# GD32.net
KiCad netlist of a schematic drawn in Altium Designer
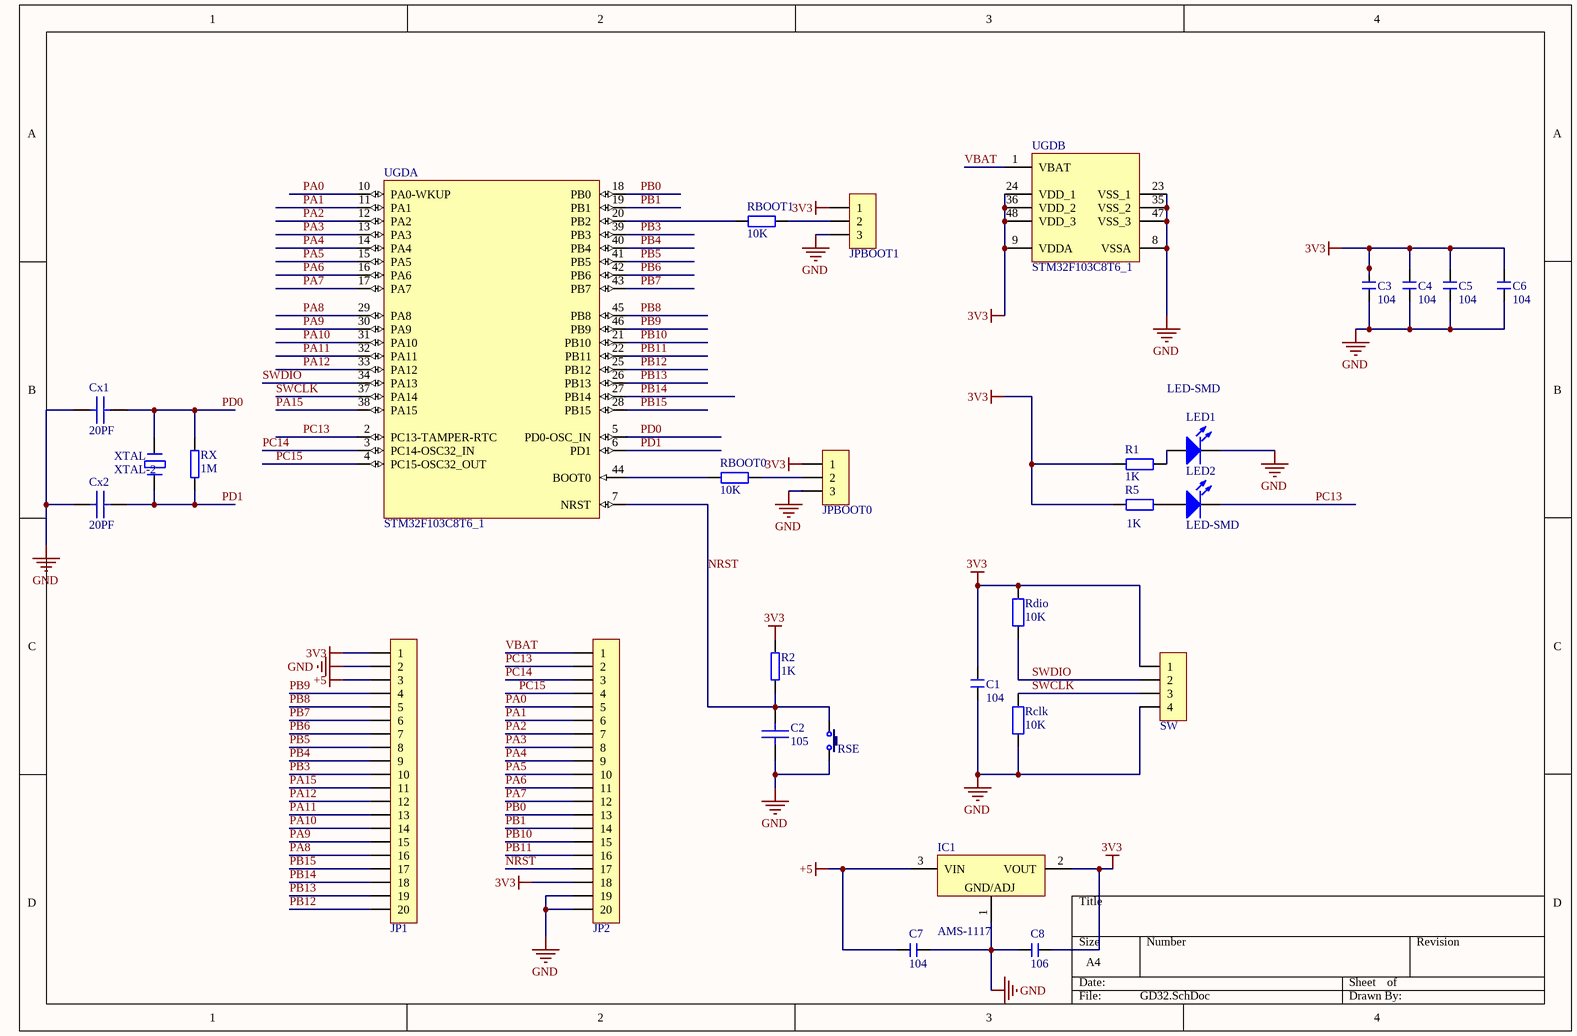
[diagram p0: GD32.SchDoc]

(export (version "E")
  (design (tool "Eeschema 10.0.6"))
  (components
    (comp (ref "C1")
      (value "104")
      (footprint "C 0805")
      (description "无极性贴片电容")
      (fields (field (name "版权归属") "源创客"))
      (libsource (lib "电阻-电容-电感") (part "C"))
    )
    (comp (ref "C2")
      (value "105")
      (footprint "LC-0805_C")
      (description "贴片电容（无极性）")
      (libsource (lib "FLY") (part "CAP-NPL-SMD"))
    )
    (comp (ref "C3")
      (value "104")
      (footprint "C 0805")
      (description "无极性贴片电容")
      (fields (field (name "版权归属") "源创客"))
      (libsource (lib "电阻-电容-电感") (part "C"))
    )
    (comp (ref "C4")
      (value "104")
      (footprint "C 0805")
      (description "无极性贴片电容")
      (fields (field (name "版权归属") "源创客"))
      (libsource (lib "电阻-电容-电感") (part "C"))
    )
    (comp (ref "C5")
      (value "104")
      (footprint "C 0805")
      (description "无极性贴片电容")
      (fields (field (name "版权归属") "源创客"))
      (libsource (lib "电阻-电容-电感") (part "C"))
    )
    (comp (ref "C6")
      (value "104")
      (footprint "C 0805")
      (description "无极性贴片电容")
      (fields (field (name "版权归属") "源创客"))
      (libsource (lib "电阻-电容-电感") (part "C"))
    )
    (comp (ref "C7")
      (value "104")
      (footprint "C 0805")
      (description "无极性贴片电容")
      (fields (field (name "版权归属") "源创客"))
      (libsource (lib "电阻-电容-电感") (part "C"))
    )
    (comp (ref "C8")
      (value "106")
      (footprint "C 0805")
      (description "无极性贴片电容")
      (fields (field (name "版权归属") "源创客"))
      (libsource (lib "电阻-电容-电感") (part "C"))
    )
    (comp (ref "Cx1")
      (value "20PF")
      (footprint "LC-0805_C")
      (description "贴片电容（无极性）")
      (libsource (lib "FLY") (part "CAP-NPL-SMD"))
    )
    (comp (ref "Cx2")
      (value "20PF")
      (footprint "LC-0805_C")
      (description "贴片电容（无极性）")
      (libsource (lib "FLY") (part "CAP-NPL-SMD"))
    )
    (comp (ref "IC1")
      (value "AMS-1117")
      (footprint "LC-SOT-223")
      (description "线性稳压器")
      (libsource (lib "FLY") (part "AMS-1117"))
    )
    (comp (ref "JP1")
      (value "HDR-1X20")
      (footprint "HDR-1X20")
      (description "20P接插件")
      (fields (field (name "版权归属") "源创客"))
      (libsource (lib "接插件") (part "Header 20"))
    )
    (comp (ref "JP2")
      (value "HDR-1X20")
      (footprint "HDR-1X20")
      (description "20P接插件")
      (fields (field (name "版权归属") "源创客"))
      (libsource (lib "接插件") (part "Header 20"))
    )
    (comp (ref "JPBOOT0")
      (value "HDR-1X3")
      (footprint "HDR-1X3")
      (description "3P接插件")
      (fields (field (name "版权归属") "源创客"))
      (libsource (lib "接插件") (part "Header 3"))
    )
    (comp (ref "JPBOOT1")
      (value "HDR-1X3")
      (footprint "HDR-1X3")
      (description "3P接插件")
      (fields (field (name "版权归属") "源创客"))
      (libsource (lib "接插件") (part "Header 3"))
    )
    (comp (ref "LED1")
      (value "LED-SMD")
      (footprint "LC-0805_LED_S1")
      (description "贴片LED")
      (fields
        (field (name "MANUFACTURER") "Generic Components")
        (field (name "PUBLISHER") "Altium Hobart Technology Centre")
      )
      (libsource (lib "FLY") (part "LED-SMD"))
    )
    (comp (ref "LED2")
      (value "LED-SMD")
      (footprint "LC-0805_LED_S1")
      (description "贴片LED")
      (fields
        (field (name "MANUFACTURER") "Generic Components")
        (field (name "PUBLISHER") "Altium Hobart Technology Centre")
      )
      (libsource (lib "FLY") (part "LED-SMD"))
    )
    (comp (ref "R1")
      (value "1K")
      (footprint "R 0805")
      (description "贴片电阻")
      (fields (field (name "版权归属") "源创客"))
      (libsource (lib "电阻-电容-电感") (part "R"))
    )
    (comp (ref "R2")
      (value "1K")
      (footprint "LC-0805_R")
      (description "电阻")
      (libsource (lib "FLY") (part "RES"))
    )
    (comp (ref "R5")
      (value "1K")
      (footprint "R 0805")
      (description "贴片电阻")
      (fields (field (name "版权归属") "源创客"))
      (libsource (lib "电阻-电容-电感") (part "R"))
    )
    (comp (ref "RBOOT0")
      (value "10K")
      (footprint "R 0805")
      (description "贴片电阻")
      (fields (field (name "版权归属") "源创客"))
      (libsource (lib "电阻-电容-电感") (part "R"))
    )
    (comp (ref "RBOOT1")
      (value "10K")
      (footprint "R 0805")
      (description "贴片电阻")
      (fields (field (name "版权归属") "源创客"))
      (libsource (lib "电阻-电容-电感") (part "R"))
    )
    (comp (ref "Rclk")
      (value "10K")
      (footprint "R 0805")
      (description "贴片电阻")
      (fields (field (name "版权归属") "源创客"))
      (libsource (lib "电阻-电容-电感") (part "R"))
    )
    (comp (ref "Rdio")
      (value "10K")
      (footprint "R 0805")
      (description "贴片电阻")
      (fields (field (name "版权归属") "源创客"))
      (libsource (lib "电阻-电容-电感") (part "R"))
    )
    (comp (ref "RSE")
      (value "3x6x5")
      (footprint "TSW SMD-3*6*2.5")
      (description "3x6轻触开关")
      (fields (field (name "版权归属") "源创客"))
      (libsource (lib "按键-开关") (part "TSW 3x6"))
    )
    (comp (ref "RX")
      (value "1M")
      (footprint "LC-0805_R")
      (description "电阻")
      (libsource (lib "FLY") (part "RES"))
    )
    (comp (ref "SW")
      (value "HDR-1X4")
      (footprint "HDR-1X4")
      (description "4P接插件")
      (fields (field (name "版权归属") "源创客"))
      (libsource (lib "接插件") (part "Header 4"))
    )
    (comp (ref "UGD")
      (value "STM32F103C8T6_1")
      (footprint "LQFP48 7X7_M")
      (description "Flaah:64/RAM:20/IO:36")
      (fields (field (name "版权归属") "源创客"))
      (libsource (lib "STM32系列单片机") (part "STM32F103C8T6_1"))
    )
    (comp (ref "XTAL")
      (value "XTAL-2")
      (footprint "LC-HC-49S")
      (description "晶体振荡器")
      (libsource (lib "FLY") (part "XTAL-2"))
    )
  )
  (nets
    (net (code "1") (name "+5") (class "Default")
      (node (ref "C7") (pin "1") (pinfunction "1_1") (pintype "passive"))
      (node (ref "IC1") (pin "3") (pinfunction "VIN_3") (pintype "passive"))
      (node (ref "JP1") (pin "3") (pinfunction "3_3") (pintype "passive"))
    )
    (net (code "2") (name "/NRST") (class "Default")
      (node (ref "C2") (pin "2") (pinfunction "2_2") (pintype "passive"))
      (node (ref "JP2") (pin "17") (pinfunction "17_17") (pintype "passive"))
      (node (ref "R2") (pin "1") (pinfunction "1_1") (pintype "passive"))
      (node (ref "RSE") (pin "1") (pinfunction "1_1") (pintype "passive"))
      (node (ref "UGD") (pin "7") (pinfunction "NRST_7") (pintype "bidirectional"))
    )
    (net (code "3") (name "/PA0") (class "Default")
      (node (ref "JP2") (pin "5") (pinfunction "5_5") (pintype "passive"))
      (node (ref "UGD") (pin "10") (pinfunction "PA0-WKUP_10") (pintype "bidirectional"))
    )
    (net (code "4") (name "/PA1") (class "Default")
      (node (ref "JP2") (pin "6") (pinfunction "6_6") (pintype "passive"))
      (node (ref "UGD") (pin "11") (pinfunction "PA1_11") (pintype "bidirectional"))
    )
    (net (code "5") (name "/PA2") (class "Default")
      (node (ref "JP2") (pin "7") (pinfunction "7_7") (pintype "passive"))
      (node (ref "UGD") (pin "12") (pinfunction "PA2_12") (pintype "bidirectional"))
    )
    (net (code "6") (name "/PA3") (class "Default")
      (node (ref "JP2") (pin "8") (pinfunction "8_8") (pintype "passive"))
      (node (ref "UGD") (pin "13") (pinfunction "PA3_13") (pintype "bidirectional"))
    )
    (net (code "7") (name "/PA4") (class "Default")
      (node (ref "JP2") (pin "9") (pinfunction "9_9") (pintype "passive"))
      (node (ref "UGD") (pin "14") (pinfunction "PA4_14") (pintype "bidirectional"))
    )
    (net (code "8") (name "/PA5") (class "Default")
      (node (ref "JP2") (pin "10") (pinfunction "10_10") (pintype "passive"))
      (node (ref "UGD") (pin "15") (pinfunction "PA5_15") (pintype "bidirectional"))
    )
    (net (code "9") (name "/PA6") (class "Default")
      (node (ref "JP2") (pin "11") (pinfunction "11_11") (pintype "passive"))
      (node (ref "UGD") (pin "16") (pinfunction "PA6_16") (pintype "bidirectional"))
    )
    (net (code "10") (name "/PA7") (class "Default")
      (node (ref "JP2") (pin "12") (pinfunction "12_12") (pintype "passive"))
      (node (ref "UGD") (pin "17") (pinfunction "PA7_17") (pintype "bidirectional"))
    )
    (net (code "11") (name "/PA8") (class "Default")
      (node (ref "JP1") (pin "16") (pinfunction "16_16") (pintype "passive"))
      (node (ref "UGD") (pin "29") (pinfunction "PA8_29") (pintype "bidirectional"))
    )
    (net (code "12") (name "/PA9") (class "Default")
      (node (ref "JP1") (pin "15") (pinfunction "15_15") (pintype "passive"))
      (node (ref "UGD") (pin "30") (pinfunction "PA9_30") (pintype "bidirectional"))
    )
    (net (code "13") (name "/PA10") (class "Default")
      (node (ref "JP1") (pin "14") (pinfunction "14_14") (pintype "passive"))
      (node (ref "UGD") (pin "31") (pinfunction "PA10_31") (pintype "bidirectional"))
    )
    (net (code "14") (name "/PA11") (class "Default")
      (node (ref "JP1") (pin "13") (pinfunction "13_13") (pintype "passive"))
      (node (ref "UGD") (pin "32") (pinfunction "PA11_32") (pintype "bidirectional"))
    )
    (net (code "15") (name "/PA12") (class "Default")
      (node (ref "JP1") (pin "12") (pinfunction "12_12") (pintype "passive"))
      (node (ref "UGD") (pin "33") (pinfunction "PA12_33") (pintype "bidirectional"))
    )
    (net (code "16") (name "/PA15") (class "Default")
      (node (ref "JP1") (pin "11") (pinfunction "11_11") (pintype "passive"))
      (node (ref "UGD") (pin "38") (pinfunction "PA15_38") (pintype "bidirectional"))
    )
    (net (code "17") (name "/PB0") (class "Default")
      (node (ref "JP2") (pin "13") (pinfunction "13_13") (pintype "passive"))
      (node (ref "UGD") (pin "18") (pinfunction "PB0_18") (pintype "bidirectional"))
    )
    (net (code "18") (name "/PB1") (class "Default")
      (node (ref "JP2") (pin "14") (pinfunction "14_14") (pintype "passive"))
      (node (ref "UGD") (pin "19") (pinfunction "PB1_19") (pintype "bidirectional"))
    )
    (net (code "19") (name "/PB3") (class "Default")
      (node (ref "JP1") (pin "10") (pinfunction "10_10") (pintype "passive"))
      (node (ref "UGD") (pin "39") (pinfunction "PB3_39") (pintype "bidirectional"))
    )
    (net (code "20") (name "/PB4") (class "Default")
      (node (ref "JP1") (pin "9") (pinfunction "9_9") (pintype "passive"))
      (node (ref "UGD") (pin "40") (pinfunction "PB4_40") (pintype "bidirectional"))
    )
    (net (code "21") (name "/PB5") (class "Default")
      (node (ref "JP1") (pin "8") (pinfunction "8_8") (pintype "passive"))
      (node (ref "UGD") (pin "41") (pinfunction "PB5_41") (pintype "bidirectional"))
    )
    (net (code "22") (name "/PB6") (class "Default")
      (node (ref "JP1") (pin "7") (pinfunction "7_7") (pintype "passive"))
      (node (ref "UGD") (pin "42") (pinfunction "PB6_42") (pintype "bidirectional"))
    )
    (net (code "23") (name "/PB7") (class "Default")
      (node (ref "JP1") (pin "6") (pinfunction "6_6") (pintype "passive"))
      (node (ref "UGD") (pin "43") (pinfunction "PB7_43") (pintype "bidirectional"))
    )
    (net (code "24") (name "/PB8") (class "Default")
      (node (ref "JP1") (pin "5") (pinfunction "5_5") (pintype "passive"))
      (node (ref "UGD") (pin "45") (pinfunction "PB8_45") (pintype "bidirectional"))
    )
    (net (code "25") (name "/PB9") (class "Default")
      (node (ref "JP1") (pin "4") (pinfunction "4_4") (pintype "passive"))
      (node (ref "UGD") (pin "46") (pinfunction "PB9_46") (pintype "bidirectional"))
    )
    (net (code "26") (name "/PB10") (class "Default")
      (node (ref "JP2") (pin "15") (pinfunction "15_15") (pintype "passive"))
      (node (ref "UGD") (pin "21") (pinfunction "PB10_21") (pintype "bidirectional"))
    )
    (net (code "27") (name "/PB11") (class "Default")
      (node (ref "JP2") (pin "16") (pinfunction "16_16") (pintype "passive"))
      (node (ref "UGD") (pin "22") (pinfunction "PB11_22") (pintype "bidirectional"))
    )
    (net (code "28") (name "/PB12") (class "Default")
      (node (ref "JP1") (pin "20") (pinfunction "20_20") (pintype "passive"))
      (node (ref "UGD") (pin "25") (pinfunction "PB12_25") (pintype "bidirectional"))
    )
    (net (code "29") (name "/PB13") (class "Default")
      (node (ref "JP1") (pin "19") (pinfunction "19_19") (pintype "passive"))
      (node (ref "UGD") (pin "26") (pinfunction "PB13_26") (pintype "bidirectional"))
    )
    (net (code "30") (name "/PB14") (class "Default")
      (node (ref "JP1") (pin "18") (pinfunction "18_18") (pintype "passive"))
      (node (ref "UGD") (pin "27") (pinfunction "PB14_27") (pintype "bidirectional"))
    )
    (net (code "31") (name "/PB15") (class "Default")
      (node (ref "JP1") (pin "17") (pinfunction "17_17") (pintype "passive"))
      (node (ref "UGD") (pin "28") (pinfunction "PB15_28") (pintype "bidirectional"))
    )
    (net (code "32") (name "/PC13") (class "Default")
      (node (ref "JP2") (pin "2") (pinfunction "2_2") (pintype "passive"))
      (node (ref "LED2") (pin "K") (pinfunction "K_K") (pintype "passive"))
      (node (ref "UGD") (pin "2") (pinfunction "PC13-TAMPER-RTC_2") (pintype "bidirectional"))
    )
    (net (code "33") (name "/PC14") (class "Default")
      (node (ref "JP2") (pin "3") (pinfunction "3_3") (pintype "passive"))
      (node (ref "UGD") (pin "3") (pinfunction "PC14-OSC32_IN_3") (pintype "bidirectional"))
    )
    (net (code "34") (name "/PC15") (class "Default")
      (node (ref "JP2") (pin "4") (pinfunction "4_4") (pintype "passive"))
      (node (ref "UGD") (pin "4") (pinfunction "PC15-OSC32_OUT_4") (pintype "bidirectional"))
    )
    (net (code "35") (name "/PD0") (class "Default")
      (node (ref "Cx1") (pin "2") (pinfunction "2_2") (pintype "passive"))
      (node (ref "RX") (pin "2") (pinfunction "2_2") (pintype "passive"))
      (node (ref "UGD") (pin "5") (pinfunction "PD0-OSC_IN_5") (pintype "bidirectional"))
      (node (ref "XTAL") (pin "2") (pinfunction "2_2") (pintype "passive"))
    )
    (net (code "36") (name "/PD1") (class "Default")
      (node (ref "Cx2") (pin "2") (pinfunction "2_2") (pintype "passive"))
      (node (ref "RX") (pin "1") (pinfunction "1_1") (pintype "passive"))
      (node (ref "UGD") (pin "6") (pinfunction "PD1_6") (pintype "bidirectional"))
      (node (ref "XTAL") (pin "1") (pinfunction "1_1") (pintype "passive"))
    )
    (net (code "37") (name "/SWCLK") (class "Default")
      (node (ref "Rclk") (pin "2") (pinfunction "2_2") (pintype "passive"))
      (node (ref "SW") (pin "3") (pinfunction "3_3") (pintype "passive"))
      (node (ref "UGD") (pin "37") (pinfunction "PA14_37") (pintype "bidirectional"))
    )
    (net (code "38") (name "/SWDIO") (class "Default")
      (node (ref "Rdio") (pin "1") (pinfunction "1_1") (pintype "passive"))
      (node (ref "SW") (pin "2") (pinfunction "2_2") (pintype "passive"))
      (node (ref "UGD") (pin "34") (pinfunction "PA13_34") (pintype "bidirectional"))
    )
    (net (code "39") (name "/VBAT") (class "Default")
      (node (ref "JP2") (pin "1") (pinfunction "1_1") (pintype "passive"))
      (node (ref "UGD") (pin "1") (pinfunction "VBAT_1") (pintype "power_in"))
    )
    (net (code "40") (name "3V3") (class "Default")
      (node (ref "C1") (pin "2") (pinfunction "2_2") (pintype "passive"))
      (node (ref "C3") (pin "2") (pinfunction "2_2") (pintype "passive"))
      (node (ref "C4") (pin "2") (pinfunction "2_2") (pintype "passive"))
      (node (ref "C5") (pin "2") (pinfunction "2_2") (pintype "passive"))
      (node (ref "C6") (pin "2") (pinfunction "2_2") (pintype "passive"))
      (node (ref "C8") (pin "2") (pinfunction "2_2") (pintype "passive"))
      (node (ref "IC1") (pin "2") (pinfunction "VOUT_2") (pintype "power_in"))
      (node (ref "JP1") (pin "1") (pinfunction "1_1") (pintype "passive"))
      (node (ref "JP2") (pin "18") (pinfunction "18_18") (pintype "passive"))
      (node (ref "JPBOOT0") (pin "1") (pinfunction "1_1") (pintype "passive"))
      (node (ref "JPBOOT1") (pin "1") (pinfunction "1_1") (pintype "passive"))
      (node (ref "R1") (pin "1") (pinfunction "1_1") (pintype "passive"))
      (node (ref "R2") (pin "2") (pinfunction "2_2") (pintype "passive"))
      (node (ref "R5") (pin "1") (pinfunction "1_1") (pintype "passive"))
      (node (ref "Rdio") (pin "2") (pinfunction "2_2") (pintype "passive"))
      (node (ref "SW") (pin "1") (pinfunction "1_1") (pintype "passive"))
      (node (ref "UGD") (pin "24") (pinfunction "VDD_1_24") (pintype "power_in"))
      (node (ref "UGD") (pin "36") (pinfunction "VDD_2_36") (pintype "power_in"))
      (node (ref "UGD") (pin "48") (pinfunction "VDD_3_48") (pintype "power_in"))
      (node (ref "UGD") (pin "9") (pinfunction "VDDA_9") (pintype "power_in"))
    )
    (net (code "41") (name "GND") (class "Default")
      (node (ref "C1") (pin "1") (pinfunction "1_1") (pintype "passive"))
      (node (ref "C2") (pin "1") (pinfunction "1_1") (pintype "passive"))
      (node (ref "C3") (pin "1") (pinfunction "1_1") (pintype "passive"))
      (node (ref "C4") (pin "1") (pinfunction "1_1") (pintype "passive"))
      (node (ref "C5") (pin "1") (pinfunction "1_1") (pintype "passive"))
      (node (ref "C6") (pin "1") (pinfunction "1_1") (pintype "passive"))
      (node (ref "C7") (pin "2") (pinfunction "2_2") (pintype "passive"))
      (node (ref "C8") (pin "1") (pinfunction "1_1") (pintype "passive"))
      (node (ref "Cx1") (pin "1") (pinfunction "1_1") (pintype "passive"))
      (node (ref "Cx2") (pin "1") (pinfunction "1_1") (pintype "passive"))
      (node (ref "IC1") (pin "1") (pinfunction "GND/ADJ_1") (pintype "passive"))
      (node (ref "JP1") (pin "2") (pinfunction "2_2") (pintype "passive"))
      (node (ref "JP2") (pin "19") (pinfunction "19_19") (pintype "passive"))
      (node (ref "JP2") (pin "20") (pinfunction "20_20") (pintype "passive"))
      (node (ref "JPBOOT0") (pin "3") (pinfunction "3_3") (pintype "passive"))
      (node (ref "JPBOOT1") (pin "3") (pinfunction "3_3") (pintype "passive"))
      (node (ref "LED1") (pin "K") (pinfunction "K_K") (pintype "passive"))
      (node (ref "RSE") (pin "2") (pinfunction "2_2") (pintype "passive"))
      (node (ref "Rclk") (pin "1") (pinfunction "1_1") (pintype "passive"))
      (node (ref "SW") (pin "4") (pinfunction "4_4") (pintype "passive"))
      (node (ref "UGD") (pin "23") (pinfunction "VSS_1_23") (pintype "power_in"))
      (node (ref "UGD") (pin "35") (pinfunction "VSS_2_35") (pintype "power_in"))
      (node (ref "UGD") (pin "47") (pinfunction "VSS_3_47") (pintype "power_in"))
      (node (ref "UGD") (pin "8") (pinfunction "VSSA_8") (pintype "power_in"))
    )
    (net (code "42") (name "Net-(JPBOOT0-Pad2)") (class "Default")
      (node (ref "JPBOOT0") (pin "2") (pinfunction "2_2") (pintype "passive"))
      (node (ref "RBOOT0") (pin "2") (pinfunction "2_2") (pintype "passive"))
    )
    (net (code "43") (name "Net-(JPBOOT1-Pad2)") (class "Default")
      (node (ref "JPBOOT1") (pin "2") (pinfunction "2_2") (pintype "passive"))
      (node (ref "RBOOT1") (pin "2") (pinfunction "2_2") (pintype "passive"))
    )
    (net (code "44") (name "Net-(LED1-PadA)") (class "Default")
      (node (ref "LED1") (pin "A") (pinfunction "A_A") (pintype "passive"))
      (node (ref "R1") (pin "2") (pinfunction "2_2") (pintype "passive"))
    )
    (net (code "45") (name "Net-(LED2-PadA)") (class "Default")
      (node (ref "LED2") (pin "A") (pinfunction "A_A") (pintype "passive"))
      (node (ref "R5") (pin "2") (pinfunction "2_2") (pintype "passive"))
    )
    (net (code "46") (name "Net-(UGDA-BOOT0)") (class "Default")
      (node (ref "RBOOT0") (pin "1") (pinfunction "1_1") (pintype "passive"))
      (node (ref "UGD") (pin "44") (pinfunction "BOOT0_44") (pintype "input"))
    )
    (net (code "47") (name "Net-(UGDA-PB2)") (class "Default")
      (node (ref "RBOOT1") (pin "1") (pinfunction "1_1") (pintype "passive"))
      (node (ref "UGD") (pin "20") (pinfunction "PB2_20") (pintype "bidirectional"))
    )
  )
)
